# SCH12.net
KiCad netlist of a schematic drawn in Altium Designer
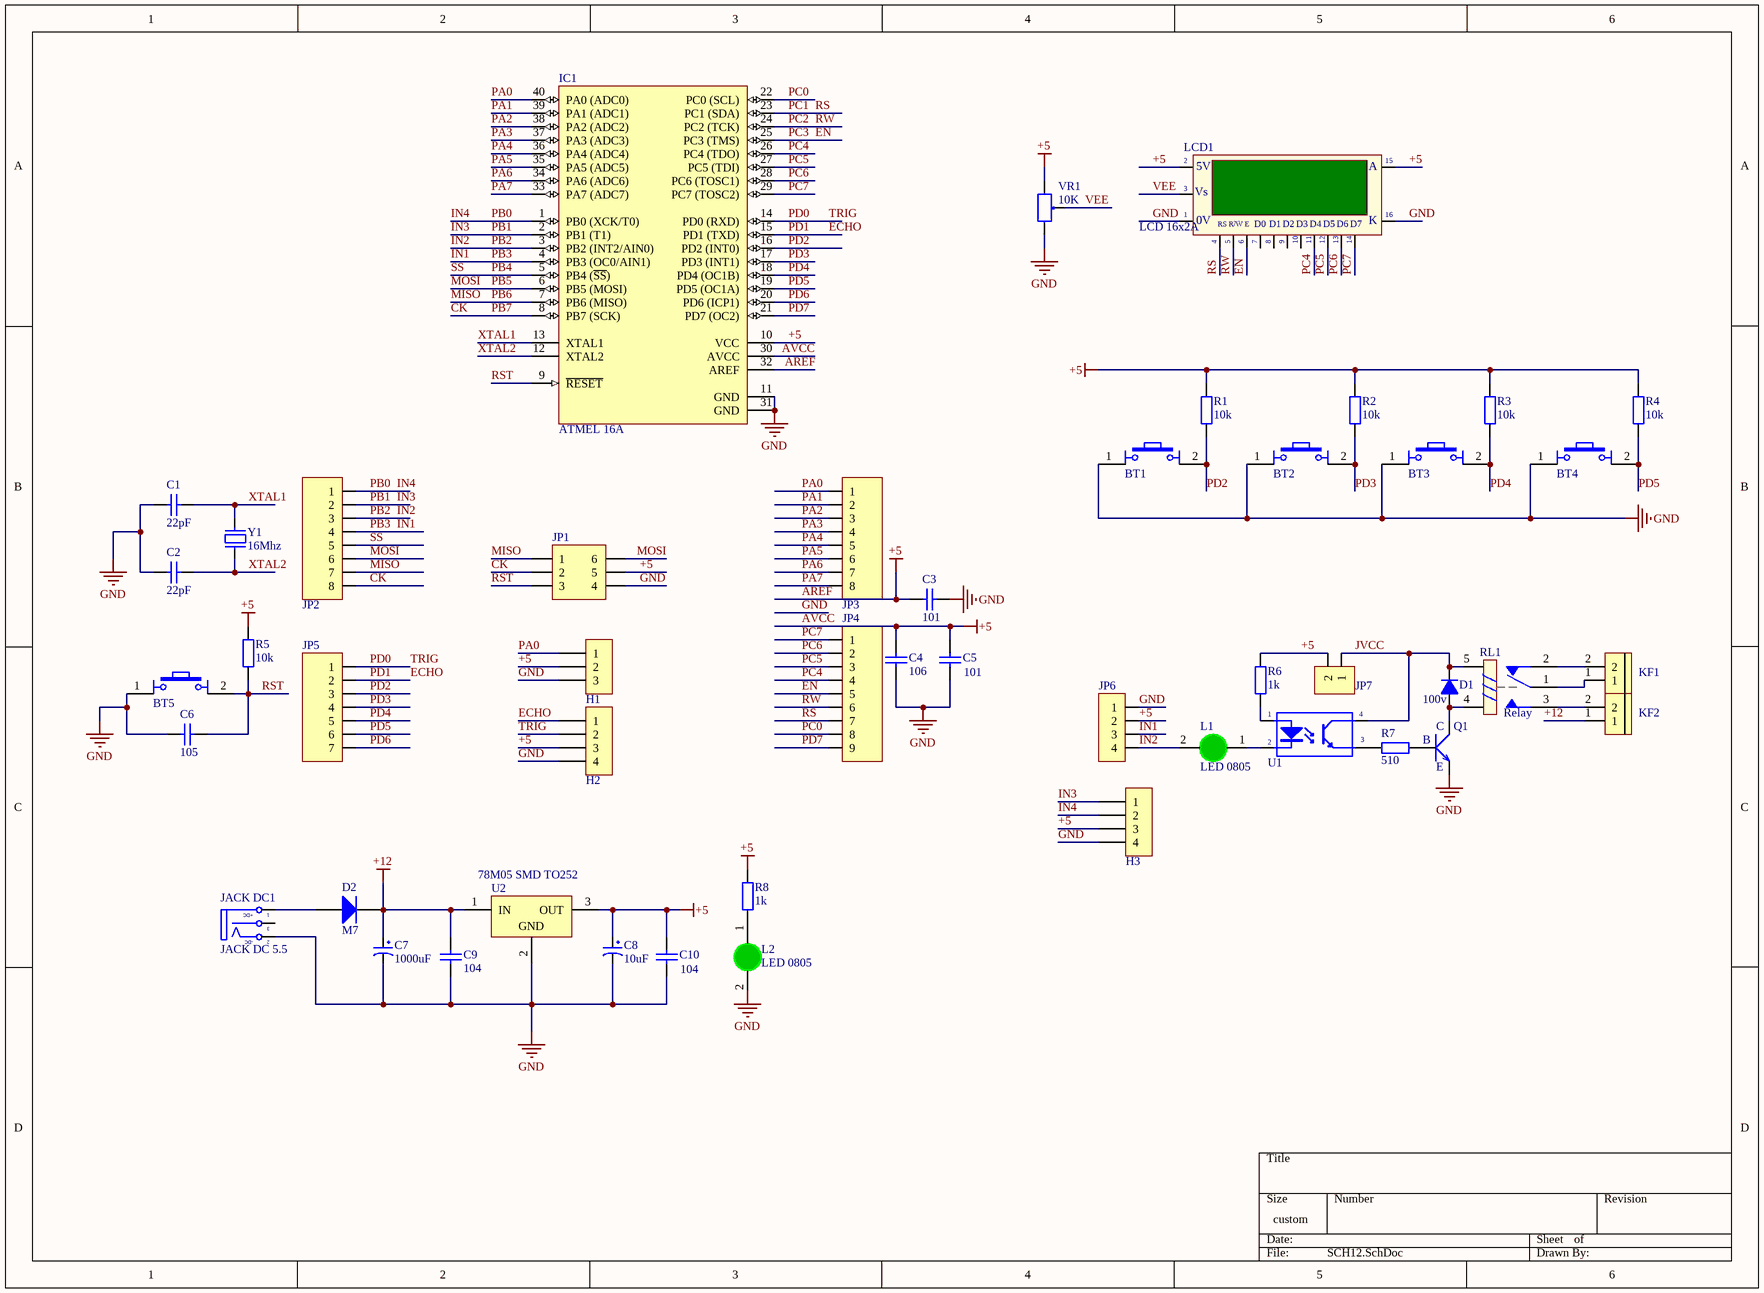
[diagram p0: SCH12.SchDoc]

(export (version "E")
  (design (tool "Eeschema 10.0.6"))
  (components
    (comp (ref "BT1")
      (value "Nut Nhan 4 Chan Cam 6x6")
      (footprint "Nut Nhan 4 Chan Cam 6x6")
      (description "Nut Nhan 4 Chan 6x6mm")
      (libsource (lib "Component") (part "Nut Nhan 4 Chan Cam 6x6"))
    )
    (comp (ref "BT2")
      (value "Nut Nhan 4 Chan Cam 6x6")
      (footprint "Nut Nhan 4 Chan Cam 6x6")
      (description "Nut Nhan 4 Chan 6x6mm")
      (libsource (lib "Component") (part "Nut Nhan 4 Chan Cam 6x6"))
    )
    (comp (ref "BT3")
      (value "Nut Nhan 4 Chan Cam 6x6")
      (footprint "Nut Nhan 4 Chan Cam 6x6")
      (description "Nut Nhan 4 Chan 6x6mm")
      (libsource (lib "Component") (part "Nut Nhan 4 Chan Cam 6x6"))
    )
    (comp (ref "BT4")
      (value "Nut Nhan 4 Chan Cam 6x6")
      (footprint "Nut Nhan 4 Chan Cam 6x6")
      (description "Nut Nhan 4 Chan 6x6mm")
      (libsource (lib "Component") (part "Nut Nhan 4 Chan Cam 6x6"))
    )
    (comp (ref "BT5")
      (value "Nut Nhan 4 Chan Cam 6x6")
      (footprint "Nut Nhan 4 Chan Cam 6x6")
      (description "Nut Nhan 4 Chan 6x6mm")
      (libsource (lib "Component") (part "Nut Nhan 4 Chan Cam 6x6"))
    )
    (comp (ref "C1")
      (value "22pF")
      (footprint "tu 0805")
      (description "Dán")
      (libsource (lib "Tu dien") (part "Tu 0805 22pF 50V 10%"))
    )
    (comp (ref "C2")
      (value "22pF")
      (footprint "tu 0805")
      (description "Dán")
      (libsource (lib "Tu dien") (part "Tu 0805 22pF 50V 10%"))
    )
    (comp (ref "C3")
      (value "101")
      (footprint "tu 0805")
      (description "Dán")
      (libsource (lib "Tu dien") (part "Tu 0805 101 50V 20%"))
    )
    (comp (ref "C4")
      (value "106")
      (footprint "tu 0805")
      (description "Dán")
      (libsource (lib "Tu dien") (part "Tu 0805 106 16V 10%"))
    )
    (comp (ref "C5")
      (value "101")
      (footprint "tu 0805")
      (description "Dán")
      (libsource (lib "Tu dien") (part "Tu 0805 101 50V 20%"))
    )
    (comp (ref "C6")
      (value "105")
      (footprint "tu 0805")
      (description "Dán")
      (libsource (lib "Tu dien") (part "Tu 0805 105 50V 10%"))
    )
    (comp (ref "C7")
      (value "1000uF")
      (footprint "tu hoa 8mm")
      (description "Cắm")
      (libsource (lib "Tu dien") (part "Tu Hoa 1000uF 16V 8x20"))
    )
    (comp (ref "C8")
      (value "10uF")
      (footprint "tu hoa 4mm")
      (description "Cắm")
      (libsource (lib "Tu dien") (part "Tu Hoa 10uF 16V 4x7"))
    )
    (comp (ref "C9")
      (value "104")
      (footprint "tu 0805")
      (description "Dán")
      (libsource (lib "Tu dien") (part "Tu 0805 104 50V 10%"))
    )
    (comp (ref "C10")
      (value "104")
      (footprint "tu 0805")
      (description "Dán")
      (libsource (lib "Tu dien") (part "Tu 0805 104 50V 10%"))
    )
    (comp (ref "D1")
      (value "100v")
      (footprint "DIODE ZENNER SMD SOD80")
      (description "Cắm")
      (libsource (lib "Diode") (part "Diode 1N4148"))
    )
    (comp (ref "D2")
      (value "M7")
      (footprint "DIODE SMA")
      (description "Dán")
      (libsource (lib "Diode") (part "Diode M7 ( 4007 )"))
    )
    (comp (ref "H1")
      (value "Header 3P 2.54 Duc Thang")
      (footprint "XH2.54M-3")
      (description "Cắm")
      (libsource (lib "Header") (part "Header 3P 2.54 Duc Thang"))
    )
    (comp (ref "H2")
      (value "Header 4P 2.54 Duc Thang")
      (footprint "XH2.54M-4")
      (description "Cắm")
      (libsource (lib "Header") (part "Header 4P 2.54 Duc Thang"))
    )
    (comp (ref "H3")
      (value "Header 4P 2.54 Duc Thang")
      (footprint "XH2.54M-4")
      (description "Cắm")
      (libsource (lib "Header") (part "Header 4P 2.54 Duc Thang"))
    )
    (comp (ref "IC1")
      (value "ATMEL 16A")
      (footprint "DIP40/W0.6")
      (description "8-Bit AVR Microcontroller with 16K Bytes of In-System Programmable Flash Memory")
      (libsource (lib "Thu Vien Chuan") (part "ATmega16A-PU"))
    )
    (comp (ref "JACK DC1")
      (value "JACK DC 5.5")
      (footprint "JACK DC 5.5")
      (libsource (lib "Component") (part "JACK DC 5.5"))
    )
    (comp (ref "JP1")
      (value "JP 2x3 2.54")
      (footprint "JP 2x3 DT")
      (description "Cắm")
      (libsource (lib "Jump") (part "JP 2x3 2.54 Duc Thang"))
    )
    (comp (ref "JP2")
      (value "JP 1x8 2.54")
      (footprint "JP 1x8 DT")
      (description "Cắm")
      (libsource (lib "Jump") (part "JP 1x8 2.54 Duc Thang"))
    )
    (comp (ref "JP3")
      (value "JP 1x8 2.54")
      (footprint "JP 1x8 DT")
      (description "Cắm")
      (libsource (lib "") (part "JP 1x8 2.54 Duc Thang_1"))
    )
    (comp (ref "JP4")
      (value "JP 1x9 2.54")
      (footprint "JP 1x9 DT")
      (description "Cắm")
      (libsource (lib "Jump") (part "JP 1x9 2.54 Duc Thang"))
    )
    (comp (ref "JP5")
      (value "JP 1x7 2.54")
      (footprint "JP 1x7 DT")
      (description "Cắm")
      (libsource (lib "Jump") (part "JP 1x7 2.54 Duc Thang"))
    )
    (comp (ref "JP6")
      (value "JP 1x4 2.54")
      (footprint "JP 1x4 DT")
      (description "Cắm")
      (libsource (lib "Jump") (part "JP 1x4 2.54 Duc Thang"))
    )
    (comp (ref "JP7")
      (value "JP 1x2 2.54")
      (footprint "JP 1x2 DT")
      (description "Cắm")
      (libsource (lib "Jump") (part "JP 1x2 2.54 Duc Thang"))
    )
    (comp (ref "KF1")
      (value "CON 2 KF301")
      (footprint "Con 2 KF301 5.08")
      (description "Cắm")
      (libsource (lib "Connector") (part "CON 2 KF301"))
    )
    (comp (ref "KF2")
      (value "CON 2 KF301")
      (footprint "Con 2 KF301 5.08")
      (description "Cắm")
      (libsource (lib "Connector") (part "CON 2 KF301"))
    )
    (comp (ref "L1")
      (value "LED 0805")
      (footprint "LED-0805-Green")
      (description "Dán")
      (libsource (lib "Led") (part "LED 0805 Xanh La"))
    )
    (comp (ref "L2")
      (value "LED 0805")
      (footprint "LED-0805-Green")
      (description "Dán")
      (libsource (lib "Led") (part "LED 0805 Xanh La"))
    )
    (comp (ref "LCD1")
      (value "LCD 16x2A")
      (footprint "LCD16X2N")
      (description "LCD dipslay 16 char, 2 line")
      (libsource (lib "Thu Vien Chuan") (part "LCD16x2A"))
    )
    (comp (ref "Q1")
      (value "SMD-TRANSISTORS-NPN-25V-500MW(SOT-23)")
      (footprint "SOT 23-3")
      (description "Bipolar (BJT) Transistor NPN 25 V 500 mA 150MHz 300 mW Surface Mount SOT-23")
      (fields (field (name "MF") "UMW") (field (name "MP") "S8050"))
      (libsource (lib "05.IC") (part "SMD-TRANSISTORS-NPN-25V-500MW(SOT-23)"))
    )
    (comp (ref "R1")
      (value "10k")
      (footprint "tro smd 0805")
      (description "Dán")
      (libsource (lib "Dien Tro") (part "Tro 0805 1% 10k"))
    )
    (comp (ref "R2")
      (value "10k")
      (footprint "tro smd 0805")
      (description "Dán")
      (libsource (lib "Dien Tro") (part "Tro 0805 1% 10k"))
    )
    (comp (ref "R3")
      (value "10k")
      (footprint "tro smd 0805")
      (description "Dán")
      (libsource (lib "Dien Tro") (part "Tro 0805 1% 10k"))
    )
    (comp (ref "R4")
      (value "10k")
      (footprint "tro smd 0805")
      (description "Dán")
      (libsource (lib "Dien Tro") (part "Tro 0805 1% 10k"))
    )
    (comp (ref "R5")
      (value "10k")
      (footprint "tro smd 0805")
      (description "Dán")
      (libsource (lib "Dien Tro") (part "Tro 0805 1% 10k"))
    )
    (comp (ref "R6")
      (value "1k")
      (footprint "tro smd 0805")
      (description "Dán")
      (libsource (lib "Dien Tro") (part "Tro 0805 1% 1k"))
    )
    (comp (ref "R7")
      (value "510")
      (footprint "tro smd 0805")
      (description "Dán")
      (libsource (lib "Dien Tro") (part "Tro 0805 1% 1k"))
    )
    (comp (ref "R8")
      (value "1k")
      (footprint "tro smd 0805")
      (description "Dán")
      (libsource (lib "Dien Tro") (part "Tro 0805 1% 1k"))
    )
    (comp (ref "RL1")
      (value "Relay")
      (footprint "Relay 5 Chan SRD")
      (description "Relay 5 Chan")
      (libsource (lib "Component") (part "Relay 5 Chan SRD"))
    )
    (comp (ref "U1")
      (value "OPTO PC817 DIP4")
      (footprint "DIP4")
      (description "Single Opto")
      (libsource (lib "IC") (part "OPTO PC817 DIP4"))
    )
    (comp (ref "U2")
      (value "78M05 SMD TO252")
      (footprint "TO252")
      (description "Dán")
      (libsource (lib "IC") (part "78M05 SMD TO252"))
    )
    (comp (ref "VR1")
      (value "10K")
      (footprint "Bien Tro Vi Chinh Dung")
      (description "Cắm")
      (libsource (lib "Dien Tro") (part "Bien Tro Tinh Chinh 1K Dung"))
    )
    (comp (ref "Y1")
      (value "16Mhz")
      (footprint "Thach Anh 2 chan cam")
      (description "Crystal For all Crystal 2pin.")
      (libsource (lib "Component") (part "Thach Anh 2 chan Cam"))
    )
  )
  (nets
    (net (code "1") (name "+5") (class "Default")
      (node (ref "C10") (pin "1") (pinfunction "1_1") (pintype "passive"))
      (node (ref "C3") (pin "1") (pinfunction "1_1") (pintype "passive"))
      (node (ref "C4") (pin "2") (pinfunction "2_2") (pintype "passive"))
      (node (ref "C5") (pin "1") (pinfunction "1_1") (pintype "passive"))
      (node (ref "C8") (pin "1") (pinfunction "1_1") (pintype "passive"))
      (node (ref "H1") (pin "2") (pinfunction "2_2") (pintype "passive"))
      (node (ref "H2") (pin "3") (pinfunction "3_3") (pintype "passive"))
      (node (ref "H3") (pin "3") (pinfunction "3_3") (pintype "passive"))
      (node (ref "IC1") (pin "10") (pinfunction "VCC_10") (pintype "power_in"))
      (node (ref "IC1") (pin "30") (pinfunction "AVCC_30") (pintype "power_in"))
      (node (ref "IC1") (pin "32") (pinfunction "AREF_32") (pintype "power_in"))
      (node (ref "JP1") (pin "5") (pinfunction "5_5") (pintype "passive"))
      (node (ref "JP6") (pin "2") (pinfunction "2_2") (pintype "passive"))
      (node (ref "JP7") (pin "2") (pinfunction "2_2") (pintype "passive"))
      (node (ref "LCD1") (pin "15") (pinfunction "A_15") (pintype "passive"))
      (node (ref "LCD1") (pin "2") (pinfunction "VDD_2") (pintype "passive"))
      (node (ref "R1") (pin "2") (pinfunction "2_2") (pintype "passive"))
      (node (ref "R2") (pin "2") (pinfunction "2_2") (pintype "passive"))
      (node (ref "R3") (pin "2") (pinfunction "2_2") (pintype "passive"))
      (node (ref "R4") (pin "2") (pinfunction "2_2") (pintype "passive"))
      (node (ref "R5") (pin "2") (pinfunction "2_2") (pintype "passive"))
      (node (ref "R6") (pin "1") (pinfunction "1_1") (pintype "passive"))
      (node (ref "R8") (pin "2") (pinfunction "2_2") (pintype "passive"))
      (node (ref "U2") (pin "3") (pinfunction "OUT_3") (pintype "power_in"))
      (node (ref "VR1") (pin "1") (pinfunction "1_1") (pintype "passive"))
    )
    (net (code "2") (name "+12") (class "Default")
      (node (ref "C7") (pin "1") (pinfunction "1_1") (pintype "passive"))
      (node (ref "C9") (pin "1") (pinfunction "1_1") (pintype "passive"))
      (node (ref "D2") (pin "2") (pinfunction "K_2") (pintype "passive"))
      (node (ref "KF2") (pin "1") (pinfunction "1_1") (pintype "passive"))
      (node (ref "U2") (pin "1") (pinfunction "IN_1") (pintype "power_in"))
    )
    (net (code "3") (name "/CK") (class "Default")
      (node (ref "IC1") (pin "8") (pinfunction "PB7_(SCK)_8") (pintype "bidirectional"))
      (node (ref "JP1") (pin "2") (pinfunction "2_2") (pintype "passive"))
      (node (ref "JP2") (pin "8") (pinfunction "8_8") (pintype "passive"))
    )
    (net (code "4") (name "/ECHO") (class "Default")
      (node (ref "H2") (pin "1") (pinfunction "1_1") (pintype "passive"))
      (node (ref "IC1") (pin "15") (pinfunction "PD1_(TXD)_15") (pintype "bidirectional"))
      (node (ref "JP5") (pin "2") (pinfunction "2_2") (pintype "passive"))
    )
    (net (code "5") (name "/EN") (class "Default")
      (node (ref "IC1") (pin "25") (pinfunction "PC3_(TMS)_25") (pintype "bidirectional"))
      (node (ref "JP4") (pin "5") (pinfunction "5_5") (pintype "passive"))
      (node (ref "LCD1") (pin "6") (pinfunction "~{EN}_6") (pintype "passive"))
    )
    (net (code "6") (name "/IN1") (class "Default")
      (node (ref "IC1") (pin "4") (pinfunction "PB3_(OC0/AIN1)_4") (pintype "bidirectional"))
      (node (ref "JP2") (pin "4") (pinfunction "4_4") (pintype "passive"))
      (node (ref "JP6") (pin "3") (pinfunction "3_3") (pintype "passive"))
    )
    (net (code "7") (name "/IN2") (class "Default")
      (node (ref "IC1") (pin "3") (pinfunction "PB2_(INT2/AIN0)_3") (pintype "bidirectional"))
      (node (ref "JP2") (pin "3") (pinfunction "3_3") (pintype "passive"))
      (node (ref "JP6") (pin "4") (pinfunction "4_4") (pintype "passive"))
      (node (ref "L1") (pin "2") (pinfunction "K_2") (pintype "passive"))
    )
    (net (code "8") (name "/IN3") (class "Default")
      (node (ref "H3") (pin "1") (pinfunction "1_1") (pintype "passive"))
      (node (ref "IC1") (pin "2") (pinfunction "PB1_(T1)_2") (pintype "bidirectional"))
      (node (ref "JP2") (pin "2") (pinfunction "2_2") (pintype "passive"))
    )
    (net (code "9") (name "/IN4") (class "Default")
      (node (ref "H3") (pin "2") (pinfunction "2_2") (pintype "passive"))
      (node (ref "IC1") (pin "1") (pinfunction "PB0_(XCK/T0)_1") (pintype "bidirectional"))
      (node (ref "JP2") (pin "1") (pinfunction "1_1") (pintype "passive"))
    )
    (net (code "10") (name "/JVCC") (class "Default")
      (node (ref "D1") (pin "2") (pinfunction "K_2") (pintype "passive"))
      (node (ref "JP7") (pin "1") (pinfunction "1_1") (pintype "passive"))
      (node (ref "RL1") (pin "5") (pinfunction "5_5") (pintype "passive"))
      (node (ref "U1") (pin "4") (pinfunction "C_4") (pintype "passive"))
    )
    (net (code "11") (name "/MISO") (class "Default")
      (node (ref "IC1") (pin "7") (pinfunction "PB6_(MISO)_7") (pintype "bidirectional"))
      (node (ref "JP1") (pin "1") (pinfunction "1_1") (pintype "passive"))
      (node (ref "JP2") (pin "7") (pinfunction "7_7") (pintype "passive"))
    )
    (net (code "12") (name "/MOSI") (class "Default")
      (node (ref "IC1") (pin "6") (pinfunction "PB5_(MOSI)_6") (pintype "bidirectional"))
      (node (ref "JP1") (pin "6") (pinfunction "6_6") (pintype "passive"))
      (node (ref "JP2") (pin "6") (pinfunction "6_6") (pintype "passive"))
    )
    (net (code "13") (name "/PA0") (class "Default")
      (node (ref "H1") (pin "1") (pinfunction "1_1") (pintype "passive"))
      (node (ref "IC1") (pin "40") (pinfunction "PA0_(ADC0)_40") (pintype "bidirectional"))
      (node (ref "JP3") (pin "1") (pinfunction "1_1") (pintype "passive"))
    )
    (net (code "14") (name "/PA1") (class "Default")
      (node (ref "IC1") (pin "39") (pinfunction "PA1_(ADC1)_39") (pintype "bidirectional"))
      (node (ref "JP3") (pin "2") (pinfunction "2_2") (pintype "passive"))
    )
    (net (code "15") (name "/PA2") (class "Default")
      (node (ref "IC1") (pin "38") (pinfunction "PA2_(ADC2)_38") (pintype "bidirectional"))
      (node (ref "JP3") (pin "3") (pinfunction "3_3") (pintype "passive"))
    )
    (net (code "16") (name "/PA3") (class "Default")
      (node (ref "IC1") (pin "37") (pinfunction "PA3_(ADC3)_37") (pintype "bidirectional"))
      (node (ref "JP3") (pin "4") (pinfunction "4_4") (pintype "passive"))
    )
    (net (code "17") (name "/PA4") (class "Default")
      (node (ref "IC1") (pin "36") (pinfunction "PA4_(ADC4)_36") (pintype "bidirectional"))
      (node (ref "JP3") (pin "5") (pinfunction "5_5") (pintype "passive"))
    )
    (net (code "18") (name "/PA5") (class "Default")
      (node (ref "IC1") (pin "35") (pinfunction "PA5_(ADC5)_35") (pintype "bidirectional"))
      (node (ref "JP3") (pin "6") (pinfunction "6_6") (pintype "passive"))
    )
    (net (code "19") (name "/PA6") (class "Default")
      (node (ref "IC1") (pin "34") (pinfunction "PA6_(ADC6)_34") (pintype "bidirectional"))
      (node (ref "JP3") (pin "7") (pinfunction "7_7") (pintype "passive"))
    )
    (net (code "20") (name "/PA7") (class "Default")
      (node (ref "IC1") (pin "33") (pinfunction "PA7_(ADC7)_33") (pintype "bidirectional"))
      (node (ref "JP3") (pin "8") (pinfunction "8_8") (pintype "passive"))
    )
    (net (code "21") (name "/PB4") (class "Default")
      (node (ref "IC1") (pin "5") (pinfunction "PB4_(~{SS})_5") (pintype "bidirectional"))
      (node (ref "JP2") (pin "5") (pinfunction "5_5") (pintype "passive"))
    )
    (net (code "22") (name "/PC0") (class "Default")
      (node (ref "IC1") (pin "22") (pinfunction "PC0_(SCL)_22") (pintype "bidirectional"))
      (node (ref "JP4") (pin "8") (pinfunction "8_8") (pintype "passive"))
    )
    (net (code "23") (name "/PC1") (class "Default")
      (node (ref "IC1") (pin "23") (pinfunction "PC1_(SDA)_23") (pintype "bidirectional"))
      (node (ref "JP4") (pin "7") (pinfunction "7_7") (pintype "passive"))
      (node (ref "LCD1") (pin "4") (pinfunction "RS_4") (pintype "passive"))
    )
    (net (code "24") (name "/PC2") (class "Default")
      (node (ref "IC1") (pin "24") (pinfunction "PC2_(TCK)_24") (pintype "bidirectional"))
      (node (ref "JP4") (pin "6") (pinfunction "6_6") (pintype "passive"))
      (node (ref "LCD1") (pin "5") (pinfunction "R/~{W}_5") (pintype "passive"))
    )
    (net (code "25") (name "/PC4") (class "Default")
      (node (ref "IC1") (pin "26") (pinfunction "PC4_(TDO)_26") (pintype "bidirectional"))
      (node (ref "JP4") (pin "4") (pinfunction "4_4") (pintype "passive"))
      (node (ref "LCD1") (pin "11") (pinfunction "D4_11") (pintype "passive"))
    )
    (net (code "26") (name "/PC5") (class "Default")
      (node (ref "IC1") (pin "27") (pinfunction "PC5_(TDI)_27") (pintype "bidirectional"))
      (node (ref "JP4") (pin "3") (pinfunction "3_3") (pintype "passive"))
      (node (ref "LCD1") (pin "12") (pinfunction "D5_12") (pintype "passive"))
    )
    (net (code "27") (name "/PC6") (class "Default")
      (node (ref "IC1") (pin "28") (pinfunction "PC6_(TOSC1)_28") (pintype "bidirectional"))
      (node (ref "JP4") (pin "2") (pinfunction "2_2") (pintype "passive"))
      (node (ref "LCD1") (pin "13") (pinfunction "D6_13") (pintype "passive"))
    )
    (net (code "28") (name "/PC7") (class "Default")
      (node (ref "IC1") (pin "29") (pinfunction "PC7_(TOSC2)_29") (pintype "bidirectional"))
      (node (ref "JP4") (pin "1") (pinfunction "1_1") (pintype "passive"))
      (node (ref "LCD1") (pin "14") (pinfunction "D7_14") (pintype "passive"))
    )
    (net (code "29") (name "/PD0") (class "Default")
      (node (ref "H2") (pin "2") (pinfunction "2_2") (pintype "passive"))
      (node (ref "IC1") (pin "14") (pinfunction "PD0_(RXD)_14") (pintype "bidirectional"))
      (node (ref "JP5") (pin "1") (pinfunction "1_1") (pintype "passive"))
    )
    (net (code "30") (name "/PD2") (class "Default")
      (node (ref "BT1") (pin "2") (pintype "passive"))
      (node (ref "IC1") (pin "16") (pinfunction "PD2_(INT0)_16") (pintype "bidirectional"))
      (node (ref "JP5") (pin "3") (pinfunction "3_3") (pintype "passive"))
      (node (ref "R1") (pin "1") (pinfunction "1_1") (pintype "passive"))
    )
    (net (code "31") (name "/PD3") (class "Default")
      (node (ref "BT2") (pin "2") (pintype "passive"))
      (node (ref "IC1") (pin "17") (pinfunction "PD3_(INT1)_17") (pintype "bidirectional"))
      (node (ref "JP5") (pin "4") (pinfunction "4_4") (pintype "passive"))
      (node (ref "R2") (pin "1") (pinfunction "1_1") (pintype "passive"))
    )
    (net (code "32") (name "/PD4") (class "Default")
      (node (ref "BT3") (pin "2") (pintype "passive"))
      (node (ref "IC1") (pin "18") (pinfunction "PD4_(OC1B)_18") (pintype "bidirectional"))
      (node (ref "JP5") (pin "5") (pinfunction "5_5") (pintype "passive"))
      (node (ref "R3") (pin "1") (pinfunction "1_1") (pintype "passive"))
    )
    (net (code "33") (name "/PD5") (class "Default")
      (node (ref "BT4") (pin "2") (pintype "passive"))
      (node (ref "IC1") (pin "19") (pinfunction "PD5_(OC1A)_19") (pintype "bidirectional"))
      (node (ref "JP5") (pin "6") (pinfunction "6_6") (pintype "passive"))
      (node (ref "R4") (pin "1") (pinfunction "1_1") (pintype "passive"))
    )
    (net (code "34") (name "/PD6") (class "Default")
      (node (ref "IC1") (pin "20") (pinfunction "PD6_(ICP1)_20") (pintype "bidirectional"))
      (node (ref "JP5") (pin "7") (pinfunction "7_7") (pintype "passive"))
    )
    (net (code "35") (name "/PD7") (class "Default")
      (node (ref "IC1") (pin "21") (pinfunction "PD7_(OC2)_21") (pintype "bidirectional"))
      (node (ref "JP4") (pin "9") (pinfunction "9_9") (pintype "passive"))
    )
    (net (code "36") (name "/RST") (class "Default")
      (node (ref "BT5") (pin "2") (pintype "passive"))
      (node (ref "C6") (pin "2") (pinfunction "2_2") (pintype "passive"))
      (node (ref "IC1") (pin "9") (pinfunction "~{RESET}_9") (pintype "input"))
      (node (ref "JP1") (pin "3") (pinfunction "3_3") (pintype "passive"))
      (node (ref "R5") (pin "1") (pinfunction "1_1") (pintype "passive"))
    )
    (net (code "37") (name "/VEE") (class "Default")
      (node (ref "LCD1") (pin "3") (pinfunction "VEE_3") (pintype "passive"))
      (node (ref "VR1") (pin "2") (pinfunction "2_2") (pintype "passive"))
    )
    (net (code "38") (name "/XTAL1") (class "Default")
      (node (ref "C1") (pin "1") (pinfunction "1_1") (pintype "passive"))
      (node (ref "IC1") (pin "13") (pinfunction "XTAL1_13") (pintype "passive"))
      (node (ref "Y1") (pin "2") (pinfunction "2_2") (pintype "passive"))
    )
    (net (code "39") (name "/XTAL2") (class "Default")
      (node (ref "C2") (pin "1") (pinfunction "1_1") (pintype "passive"))
      (node (ref "IC1") (pin "12") (pinfunction "XTAL2_12") (pintype "passive"))
      (node (ref "Y1") (pin "1") (pinfunction "1_1") (pintype "passive"))
    )
    (net (code "40") (name "GND") (class "Default")
      (node (ref "BT1") (pin "1") (pintype "passive"))
      (node (ref "BT2") (pin "1") (pintype "passive"))
      (node (ref "BT3") (pin "1") (pintype "passive"))
      (node (ref "BT4") (pin "1") (pintype "passive"))
      (node (ref "BT5") (pin "1") (pintype "passive"))
      (node (ref "C1") (pin "2") (pinfunction "2_2") (pintype "passive"))
      (node (ref "C10") (pin "2") (pinfunction "2_2") (pintype "passive"))
      (node (ref "C2") (pin "2") (pinfunction "2_2") (pintype "passive"))
      (node (ref "C3") (pin "2") (pinfunction "2_2") (pintype "passive"))
      (node (ref "C4") (pin "1") (pinfunction "1_1") (pintype "passive"))
      (node (ref "C5") (pin "2") (pinfunction "2_2") (pintype "passive"))
      (node (ref "C6") (pin "1") (pinfunction "1_1") (pintype "passive"))
      (node (ref "C7") (pin "2") (pinfunction "2_2") (pintype "passive"))
      (node (ref "C8") (pin "2") (pinfunction "2_2") (pintype "passive"))
      (node (ref "C9") (pin "2") (pinfunction "2_2") (pintype "passive"))
      (node (ref "H1") (pin "3") (pinfunction "3_3") (pintype "passive"))
      (node (ref "H2") (pin "4") (pinfunction "4_4") (pintype "passive"))
      (node (ref "H3") (pin "4") (pinfunction "4_4") (pintype "passive"))
      (node (ref "IC1") (pin "11") (pinfunction "GND_11") (pintype "power_in"))
      (node (ref "IC1") (pin "31") (pinfunction "GND_31") (pintype "power_in"))
      (node (ref "JACK DC1") (pin "2") (pinfunction "TN_2") (pintype "passive"))
      (node (ref "JP1") (pin "4") (pinfunction "4_4") (pintype "passive"))
      (node (ref "JP6") (pin "1") (pinfunction "1_1") (pintype "passive"))
      (node (ref "L2") (pin "2") (pinfunction "K_2") (pintype "passive"))
      (node (ref "LCD1") (pin "1") (pinfunction "GND_1") (pintype "passive"))
      (node (ref "LCD1") (pin "16") (pinfunction "K_16") (pintype "passive"))
      (node (ref "Q1") (pin "2") (pinfunction "E_2") (pintype "passive"))
      (node (ref "U2") (pin "2") (pinfunction "GND_2") (pintype "power_in"))
      (node (ref "VR1") (pin "3") (pinfunction "3_3") (pintype "passive"))
    )
    (net (code "41") (name "Net-(D1-A)") (class "Default")
      (node (ref "D1") (pin "1") (pinfunction "A_1") (pintype "passive"))
      (node (ref "Q1") (pin "3") (pinfunction "C_3") (pintype "passive"))
      (node (ref "RL1") (pin "4") (pinfunction "4_4") (pintype "passive"))
    )
    (net (code "42") (name "Net-(D2-A)") (class "Default")
      (node (ref "D2") (pin "1") (pinfunction "A_1") (pintype "passive"))
      (node (ref "JACK DC1") (pin "1") (pinfunction "T_1") (pintype "passive"))
    )
    (net (code "43") (name "Net-(KF1-Pad1)") (class "Default")
      (node (ref "KF1") (pin "1") (pinfunction "1_1") (pintype "passive"))
      (node (ref "RL1") (pin "1") (pinfunction "1_1") (pintype "passive"))
    )
    (net (code "44") (name "Net-(KF1-Pad2)") (class "Default")
      (node (ref "KF1") (pin "2") (pinfunction "2_2") (pintype "passive"))
      (node (ref "RL1") (pin "2") (pinfunction "2_2") (pintype "passive"))
    )
    (net (code "45") (name "Net-(KF2-Pad2)") (class "Default")
      (node (ref "KF2") (pin "2") (pinfunction "2_2") (pintype "passive"))
      (node (ref "RL1") (pin "3") (pinfunction "3_3") (pintype "passive"))
    )
    (net (code "46") (name "Net-(L1-A)") (class "Default")
      (node (ref "L1") (pin "1") (pinfunction "A_1") (pintype "passive"))
      (node (ref "U1") (pin "2") (pinfunction "K_2") (pintype "passive"))
    )
    (net (code "47") (name "Net-(L2-A)") (class "Default")
      (node (ref "L2") (pin "1") (pinfunction "A_1") (pintype "passive"))
      (node (ref "R8") (pin "1") (pinfunction "1_1") (pintype "passive"))
    )
    (net (code "48") (name "Net-(Q1-B)") (class "Default")
      (node (ref "Q1") (pin "1") (pinfunction "B_1") (pintype "passive"))
      (node (ref "R7") (pin "1") (pinfunction "1_1") (pintype "passive"))
    )
    (net (code "49") (name "Net-(U1-A)") (class "Default")
      (node (ref "R6") (pin "2") (pinfunction "2_2") (pintype "passive"))
      (node (ref "U1") (pin "1") (pinfunction "A_1") (pintype "passive"))
    )
    (net (code "50") (name "Net-(U1-E)") (class "Default")
      (node (ref "R7") (pin "2") (pinfunction "2_2") (pintype "passive"))
      (node (ref "U1") (pin "3") (pinfunction "E_3") (pintype "passive"))
    )
    (net (code "51") (name "unconnected-(JACK DC1-S-Pad3)") (class "Default")
      (node (ref "JACK DC1") (pin "3") (pinfunction "S_3") (pintype "power_in"))
    )
    (net (code "52") (name "unconnected-(LCD1-D0-Pad7)") (class "Default")
      (node (ref "LCD1") (pin "7") (pinfunction "D0_7") (pintype "passive"))
    )
    (net (code "53") (name "unconnected-(LCD1-D1-Pad8)") (class "Default")
      (node (ref "LCD1") (pin "8") (pinfunction "D1_8") (pintype "passive"))
    )
    (net (code "54") (name "unconnected-(LCD1-D2-Pad9)") (class "Default")
      (node (ref "LCD1") (pin "9") (pinfunction "D2_9") (pintype "passive"))
    )
    (net (code "55") (name "unconnected-(LCD1-D3-Pad10)") (class "Default")
      (node (ref "LCD1") (pin "10") (pinfunction "D3_10") (pintype "passive"))
    )
  )
)
